# Schematico_PCL.net
KiCad netlist of a schematic drawn in Altium Designer
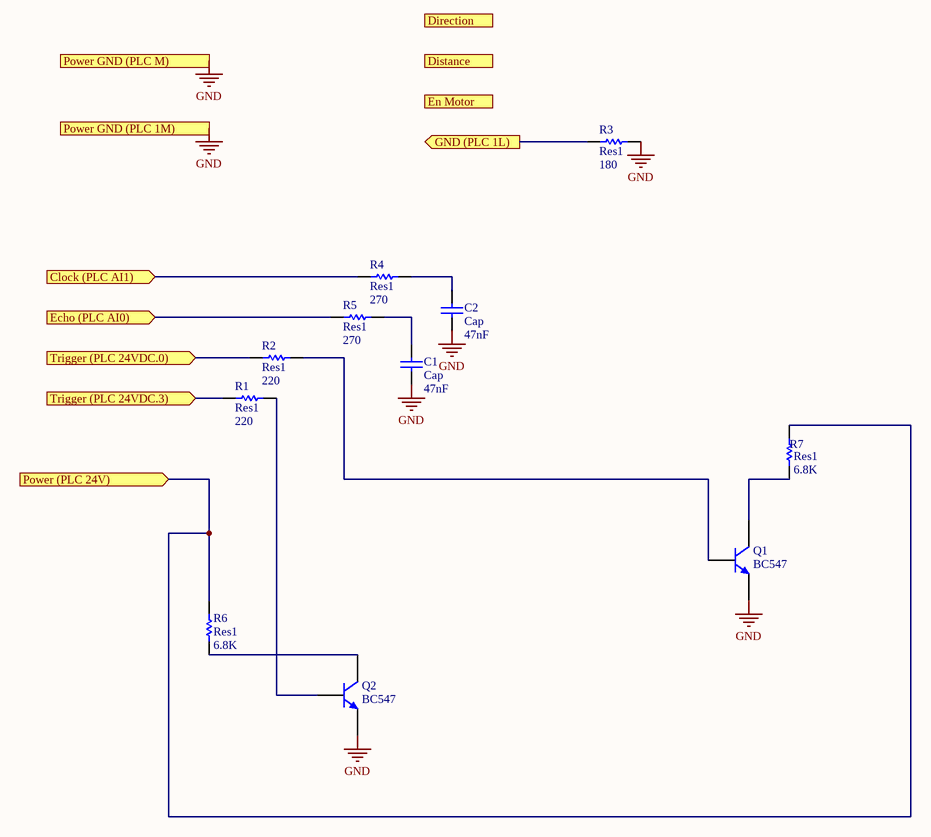
[diagram p0: Schematico_PCL.SchDoc]

(export (version "E")
  (design (tool "Eeschema 10.0.6"))
  (components
    (comp (ref "C1")
      (value "Cap")
      (footprint "RAD-0.3")
      (description "Capacitor")
      (fields (field (name "ALTIUM_VALUE") "47nF") (field (name "PUBLISHER") "Altium Limited"))
      (libsource (lib "Miscellaneous Devices") (part "Cap"))
    )
    (comp (ref "C2")
      (value "Cap")
      (footprint "RAD-0.3")
      (description "Capacitor")
      (fields (field (name "ALTIUM_VALUE") "47nF") (field (name "PUBLISHER") "Altium Limited"))
      (libsource (lib "Miscellaneous Devices") (part "Cap"))
    )
    (comp (ref "Q1")
      (value "BC547")
      (footprint "TO-226-AA")
      (description "NPN Bipolar Transistor")
      (fields (field (name "PUBLISHER") "Altium Limited"))
      (libsource (lib "Miscellaneous Devices") (part "NPN"))
    )
    (comp (ref "Q2")
      (value "BC547")
      (footprint "TO-226-AA")
      (description "NPN Bipolar Transistor")
      (fields (field (name "PUBLISHER") "Altium Limited"))
      (libsource (lib "Miscellaneous Devices") (part "NPN"))
    )
    (comp (ref "R1")
      (value "Res1")
      (footprint "AXIAL-0.3")
      (description "Resistor")
      (fields (field (name "ALTIUM_VALUE") "220") (field (name "PUBLISHER") "Altium Limited"))
      (libsource (lib "Miscellaneous Devices") (part "Res1"))
    )
    (comp (ref "R2")
      (value "Res1")
      (footprint "AXIAL-0.3")
      (description "Resistor")
      (fields (field (name "ALTIUM_VALUE") "220") (field (name "PUBLISHER") "Altium Limited"))
      (libsource (lib "Miscellaneous Devices") (part "Res1"))
    )
    (comp (ref "R3")
      (value "Res1")
      (footprint "AXIAL-0.3")
      (description "Resistor")
      (fields (field (name "ALTIUM_VALUE") "180") (field (name "PUBLISHER") "Altium Limited"))
      (libsource (lib "Miscellaneous Devices") (part "Res1"))
    )
    (comp (ref "R4")
      (value "Res1")
      (footprint "AXIAL-0.3")
      (description "Resistor")
      (fields (field (name "ALTIUM_VALUE") "270") (field (name "PUBLISHER") "Altium Limited"))
      (libsource (lib "Miscellaneous Devices") (part "Res1"))
    )
    (comp (ref "R5")
      (value "Res1")
      (footprint "AXIAL-0.3")
      (description "Resistor")
      (fields (field (name "ALTIUM_VALUE") "270") (field (name "PUBLISHER") "Altium Limited"))
      (libsource (lib "Miscellaneous Devices") (part "Res1"))
    )
    (comp (ref "R6")
      (value "Res1")
      (footprint "AXIAL-0.3")
      (description "Resistor")
      (fields (field (name "ALTIUM_VALUE") "6.8K") (field (name "PUBLISHER") "Altium Limited"))
      (libsource (lib "Miscellaneous Devices") (part "Res1"))
    )
    (comp (ref "R7")
      (value "Res1")
      (footprint "AXIAL-0.3")
      (description "Resistor")
      (fields (field (name "ALTIUM_VALUE") "6.8K") (field (name "PUBLISHER") "Altium Limited"))
      (libsource (lib "Miscellaneous Devices") (part "Res1"))
    )
  )
  (nets
    (net (code "1") (name "/Clock (PLC AI1)") (class "Default")
      (node (ref "R4") (pin "1") (pinfunction "1_1") (pintype "passive"))
    )
    (net (code "4") (name "/Echo (PLC AI0)") (class "Default")
      (node (ref "R5") (pin "1") (pinfunction "1_1") (pintype "passive"))
    )
    (net (code "6") (name "/GND (PLC 1L)") (class "Default")
      (node (ref "R3") (pin "1") (pinfunction "1_1") (pintype "passive"))
    )
    (net (code "7") (name "/Power (PLC 24V)") (class "Default")
      (node (ref "R6") (pin "2") (pinfunction "2_2") (pintype "passive"))
      (node (ref "R7") (pin "2") (pinfunction "2_2") (pintype "passive"))
    )
    (net (code "8") (name "/Trigger (PLC 24VDC.0)") (class "Default")
      (node (ref "R2") (pin "1") (pinfunction "1_1") (pintype "passive"))
    )
    (net (code "9") (name "/Trigger (PLC 24VDC.3)") (class "Default")
      (node (ref "R1") (pin "1") (pinfunction "1_1") (pintype "passive"))
    )
    (net (code "10") (name "GND") (class "Default")
      (node (ref "C1") (pin "1") (pinfunction "1_1") (pintype "passive"))
      (node (ref "C2") (pin "1") (pinfunction "1_1") (pintype "passive"))
      (node (ref "Q1") (pin "3") (pinfunction "E_3") (pintype "passive"))
      (node (ref "Q2") (pin "3") (pinfunction "E_3") (pintype "passive"))
      (node (ref "R3") (pin "2") (pinfunction "2_2") (pintype "passive"))
    )
    (net (code "11") (name "Net-(C1-Pad2)") (class "Default")
      (node (ref "C1") (pin "2") (pinfunction "2_2") (pintype "passive"))
      (node (ref "R5") (pin "2") (pinfunction "2_2") (pintype "passive"))
    )
    (net (code "12") (name "Net-(C2-Pad2)") (class "Default")
      (node (ref "C2") (pin "2") (pinfunction "2_2") (pintype "passive"))
      (node (ref "R4") (pin "2") (pinfunction "2_2") (pintype "passive"))
    )
    (net (code "13") (name "Net-(Q1-B)") (class "Default")
      (node (ref "Q1") (pin "2") (pinfunction "B_2") (pintype "passive"))
      (node (ref "R2") (pin "2") (pinfunction "2_2") (pintype "passive"))
    )
    (net (code "14") (name "Net-(Q1-C)") (class "Default")
      (node (ref "Q1") (pin "1") (pinfunction "C_1") (pintype "passive"))
      (node (ref "R7") (pin "1") (pinfunction "1_1") (pintype "passive"))
    )
    (net (code "15") (name "Net-(Q2-B)") (class "Default")
      (node (ref "Q2") (pin "2") (pinfunction "B_2") (pintype "passive"))
      (node (ref "R1") (pin "2") (pinfunction "2_2") (pintype "passive"))
    )
    (net (code "16") (name "Net-(Q2-C)") (class "Default")
      (node (ref "Q2") (pin "1") (pinfunction "C_1") (pintype "passive"))
      (node (ref "R6") (pin "1") (pinfunction "1_1") (pintype "passive"))
    )
  )
)
